# AutoSpielSimplified.net
KiCad netlist of a schematic drawn in EAGLE
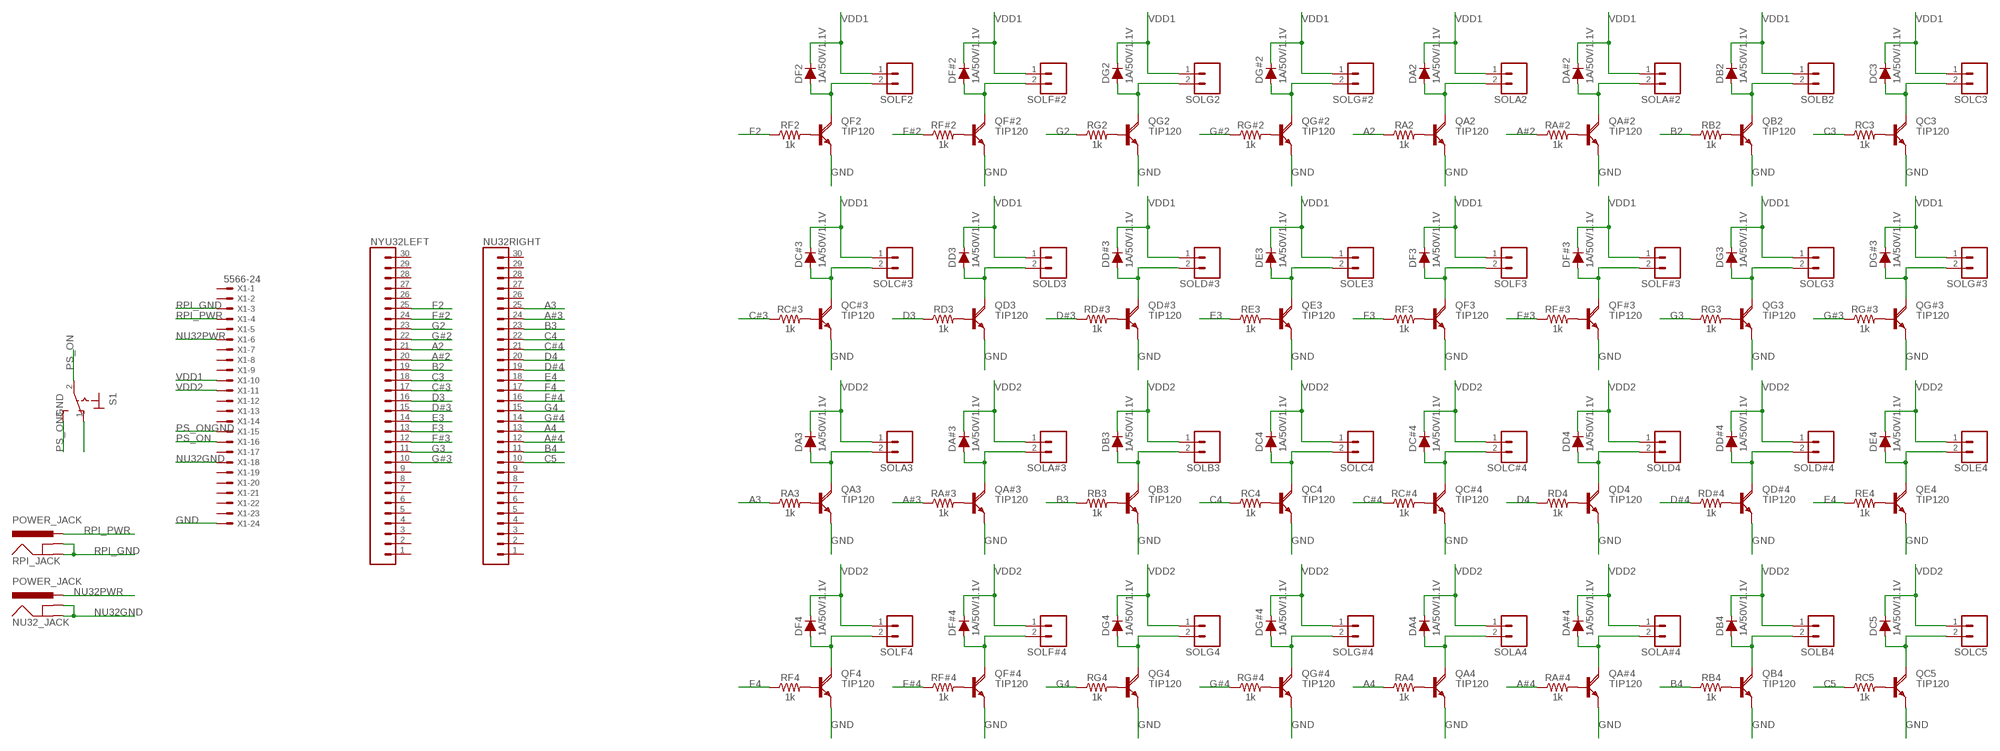
[diagram p0: schematic, sheet 1]

(export (version "E")
  (design (tool "Eeschema 10.0.6"))
  (components
    (comp (ref "DA#2")
      (value "1A/50V/1.1V")
      (footprint "eagle-import:DIODE-1N4001")
      (libsource (lib "eagle-import") (part "DIODE-PTH"))
    )
    (comp (ref "DA#3")
      (value "1A/50V/1.1V")
      (footprint "eagle-import:DIODE-1N4001")
      (libsource (lib "eagle-import") (part "DIODE-PTH"))
    )
    (comp (ref "DA#4")
      (value "1A/50V/1.1V")
      (footprint "eagle-import:DIODE-1N4001")
      (libsource (lib "eagle-import") (part "DIODE-PTH"))
    )
    (comp (ref "DA2")
      (value "1A/50V/1.1V")
      (footprint "eagle-import:DIODE-1N4001")
      (libsource (lib "eagle-import") (part "DIODE-PTH"))
    )
    (comp (ref "DA3")
      (value "1A/50V/1.1V")
      (footprint "eagle-import:DIODE-1N4001")
      (libsource (lib "eagle-import") (part "DIODE-PTH"))
    )
    (comp (ref "DA4")
      (value "1A/50V/1.1V")
      (footprint "eagle-import:DIODE-1N4001")
      (libsource (lib "eagle-import") (part "DIODE-PTH"))
    )
    (comp (ref "DB2")
      (value "1A/50V/1.1V")
      (footprint "eagle-import:DIODE-1N4001")
      (libsource (lib "eagle-import") (part "DIODE-PTH"))
    )
    (comp (ref "DB3")
      (value "1A/50V/1.1V")
      (footprint "eagle-import:DIODE-1N4001")
      (libsource (lib "eagle-import") (part "DIODE-PTH"))
    )
    (comp (ref "DB4")
      (value "1A/50V/1.1V")
      (footprint "eagle-import:DIODE-1N4001")
      (libsource (lib "eagle-import") (part "DIODE-PTH"))
    )
    (comp (ref "DC#3")
      (value "1A/50V/1.1V")
      (footprint "eagle-import:DIODE-1N4001")
      (libsource (lib "eagle-import") (part "DIODE-PTH"))
    )
    (comp (ref "DC#4")
      (value "1A/50V/1.1V")
      (footprint "eagle-import:DIODE-1N4001")
      (libsource (lib "eagle-import") (part "DIODE-PTH"))
    )
    (comp (ref "DC3")
      (value "1A/50V/1.1V")
      (footprint "eagle-import:DIODE-1N4001")
      (libsource (lib "eagle-import") (part "DIODE-PTH"))
    )
    (comp (ref "DC4")
      (value "1A/50V/1.1V")
      (footprint "eagle-import:DIODE-1N4001")
      (libsource (lib "eagle-import") (part "DIODE-PTH"))
    )
    (comp (ref "DC5")
      (value "1A/50V/1.1V")
      (footprint "eagle-import:DIODE-1N4001")
      (libsource (lib "eagle-import") (part "DIODE-PTH"))
    )
    (comp (ref "DD#3")
      (value "1A/50V/1.1V")
      (footprint "eagle-import:DIODE-1N4001")
      (libsource (lib "eagle-import") (part "DIODE-PTH"))
    )
    (comp (ref "DD#4")
      (value "1A/50V/1.1V")
      (footprint "eagle-import:DIODE-1N4001")
      (libsource (lib "eagle-import") (part "DIODE-PTH"))
    )
    (comp (ref "DD3")
      (value "1A/50V/1.1V")
      (footprint "eagle-import:DIODE-1N4001")
      (libsource (lib "eagle-import") (part "DIODE-PTH"))
    )
    (comp (ref "DD4")
      (value "1A/50V/1.1V")
      (footprint "eagle-import:DIODE-1N4001")
      (libsource (lib "eagle-import") (part "DIODE-PTH"))
    )
    (comp (ref "DE3")
      (value "1A/50V/1.1V")
      (footprint "eagle-import:DIODE-1N4001")
      (libsource (lib "eagle-import") (part "DIODE-PTH"))
    )
    (comp (ref "DE4")
      (value "1A/50V/1.1V")
      (footprint "eagle-import:DIODE-1N4001")
      (libsource (lib "eagle-import") (part "DIODE-PTH"))
    )
    (comp (ref "DF#2")
      (value "1A/50V/1.1V")
      (footprint "eagle-import:DIODE-1N4001")
      (libsource (lib "eagle-import") (part "DIODE-PTH"))
    )
    (comp (ref "DF#3")
      (value "1A/50V/1.1V")
      (footprint "eagle-import:DIODE-1N4001")
      (libsource (lib "eagle-import") (part "DIODE-PTH"))
    )
    (comp (ref "DF#4")
      (value "1A/50V/1.1V")
      (footprint "eagle-import:DIODE-1N4001")
      (libsource (lib "eagle-import") (part "DIODE-PTH"))
    )
    (comp (ref "DF2")
      (value "1A/50V/1.1V")
      (footprint "eagle-import:DIODE-1N4001")
      (libsource (lib "eagle-import") (part "DIODE-PTH"))
    )
    (comp (ref "DF3")
      (value "1A/50V/1.1V")
      (footprint "eagle-import:DIODE-1N4001")
      (libsource (lib "eagle-import") (part "DIODE-PTH"))
    )
    (comp (ref "DF4")
      (value "1A/50V/1.1V")
      (footprint "eagle-import:DIODE-1N4001")
      (libsource (lib "eagle-import") (part "DIODE-PTH"))
    )
    (comp (ref "DG#2")
      (value "1A/50V/1.1V")
      (footprint "eagle-import:DIODE-1N4001")
      (libsource (lib "eagle-import") (part "DIODE-PTH"))
    )
    (comp (ref "DG#3")
      (value "1A/50V/1.1V")
      (footprint "eagle-import:DIODE-1N4001")
      (libsource (lib "eagle-import") (part "DIODE-PTH"))
    )
    (comp (ref "DG#4")
      (value "1A/50V/1.1V")
      (footprint "eagle-import:DIODE-1N4001")
      (libsource (lib "eagle-import") (part "DIODE-PTH"))
    )
    (comp (ref "DG2")
      (value "1A/50V/1.1V")
      (footprint "eagle-import:DIODE-1N4001")
      (libsource (lib "eagle-import") (part "DIODE-PTH"))
    )
    (comp (ref "DG3")
      (value "1A/50V/1.1V")
      (footprint "eagle-import:DIODE-1N4001")
      (libsource (lib "eagle-import") (part "DIODE-PTH"))
    )
    (comp (ref "DG4")
      (value "1A/50V/1.1V")
      (footprint "eagle-import:DIODE-1N4001")
      (libsource (lib "eagle-import") (part "DIODE-PTH"))
    )
    (comp (ref "NU32RIGHT")
      (value "CONN_30")
      (footprint "eagle-import:1X30")
      (libsource (lib "eagle-import") (part "CONN_30"))
    )
    (comp (ref "NU32_JACK")
      (value "POWER_JACK")
      (footprint "eagle-import:POWER_JACK_PTH")
      (libsource (lib "eagle-import") (part "POWER_JACK"))
    )
    (comp (ref "NYU32LEFT")
      (value "CONN_30")
      (footprint "eagle-import:1X30")
      (libsource (lib "eagle-import") (part "CONN_30"))
    )
    (comp (ref "QA#2")
      (value "TIP120")
      (footprint "eagle-import:TO220AH")
      (libsource (lib "eagle-import") (part "TIP120"))
    )
    (comp (ref "QA#3")
      (value "TIP120")
      (footprint "eagle-import:TO220AH")
      (libsource (lib "eagle-import") (part "TIP120"))
    )
    (comp (ref "QA#4")
      (value "TIP120")
      (footprint "eagle-import:TO220AH")
      (libsource (lib "eagle-import") (part "TIP120"))
    )
    (comp (ref "QA2")
      (value "TIP120")
      (footprint "eagle-import:TO220AH")
      (libsource (lib "eagle-import") (part "TIP120"))
    )
    (comp (ref "QA3")
      (value "TIP120")
      (footprint "eagle-import:TO220AH")
      (libsource (lib "eagle-import") (part "TIP120"))
    )
    (comp (ref "QA4")
      (value "TIP120")
      (footprint "eagle-import:TO220AH")
      (libsource (lib "eagle-import") (part "TIP120"))
    )
    (comp (ref "QB2")
      (value "TIP120")
      (footprint "eagle-import:TO220AH")
      (libsource (lib "eagle-import") (part "TIP120"))
    )
    (comp (ref "QB3")
      (value "TIP120")
      (footprint "eagle-import:TO220AH")
      (libsource (lib "eagle-import") (part "TIP120"))
    )
    (comp (ref "QB4")
      (value "TIP120")
      (footprint "eagle-import:TO220AH")
      (libsource (lib "eagle-import") (part "TIP120"))
    )
    (comp (ref "QC#3")
      (value "TIP120")
      (footprint "eagle-import:TO220AH")
      (libsource (lib "eagle-import") (part "TIP120"))
    )
    (comp (ref "QC#4")
      (value "TIP120")
      (footprint "eagle-import:TO220AH")
      (libsource (lib "eagle-import") (part "TIP120"))
    )
    (comp (ref "QC3")
      (value "TIP120")
      (footprint "eagle-import:TO220AH")
      (libsource (lib "eagle-import") (part "TIP120"))
    )
    (comp (ref "QC4")
      (value "TIP120")
      (footprint "eagle-import:TO220AH")
      (libsource (lib "eagle-import") (part "TIP120"))
    )
    (comp (ref "QC5")
      (value "TIP120")
      (footprint "eagle-import:TO220AH")
      (libsource (lib "eagle-import") (part "TIP120"))
    )
    (comp (ref "QD#3")
      (value "TIP120")
      (footprint "eagle-import:TO220AH")
      (libsource (lib "eagle-import") (part "TIP120"))
    )
    (comp (ref "QD#4")
      (value "TIP120")
      (footprint "eagle-import:TO220AH")
      (libsource (lib "eagle-import") (part "TIP120"))
    )
    (comp (ref "QD3")
      (value "TIP120")
      (footprint "eagle-import:TO220AH")
      (libsource (lib "eagle-import") (part "TIP120"))
    )
    (comp (ref "QD4")
      (value "TIP120")
      (footprint "eagle-import:TO220AH")
      (libsource (lib "eagle-import") (part "TIP120"))
    )
    (comp (ref "QE3")
      (value "TIP120")
      (footprint "eagle-import:TO220AH")
      (libsource (lib "eagle-import") (part "TIP120"))
    )
    (comp (ref "QE4")
      (value "TIP120")
      (footprint "eagle-import:TO220AH")
      (libsource (lib "eagle-import") (part "TIP120"))
    )
    (comp (ref "QF#2")
      (value "TIP120")
      (footprint "eagle-import:TO220AH")
      (libsource (lib "eagle-import") (part "TIP120"))
    )
    (comp (ref "QF#3")
      (value "TIP120")
      (footprint "eagle-import:TO220AH")
      (libsource (lib "eagle-import") (part "TIP120"))
    )
    (comp (ref "QF#4")
      (value "TIP120")
      (footprint "eagle-import:TO220AH")
      (libsource (lib "eagle-import") (part "TIP120"))
    )
    (comp (ref "QF2")
      (value "TIP120")
      (footprint "eagle-import:TO220AH")
      (libsource (lib "eagle-import") (part "TIP120"))
    )
    (comp (ref "QF3")
      (value "TIP120")
      (footprint "eagle-import:TO220AH")
      (libsource (lib "eagle-import") (part "TIP120"))
    )
    (comp (ref "QF4")
      (value "TIP120")
      (footprint "eagle-import:TO220AH")
      (libsource (lib "eagle-import") (part "TIP120"))
    )
    (comp (ref "QG#2")
      (value "TIP120")
      (footprint "eagle-import:TO220AH")
      (libsource (lib "eagle-import") (part "TIP120"))
    )
    (comp (ref "QG#3")
      (value "TIP120")
      (footprint "eagle-import:TO220AH")
      (libsource (lib "eagle-import") (part "TIP120"))
    )
    (comp (ref "QG#4")
      (value "TIP120")
      (footprint "eagle-import:TO220AH")
      (libsource (lib "eagle-import") (part "TIP120"))
    )
    (comp (ref "QG2")
      (value "TIP120")
      (footprint "eagle-import:TO220AH")
      (libsource (lib "eagle-import") (part "TIP120"))
    )
    (comp (ref "QG3")
      (value "TIP120")
      (footprint "eagle-import:TO220AH")
      (libsource (lib "eagle-import") (part "TIP120"))
    )
    (comp (ref "QG4")
      (value "TIP120")
      (footprint "eagle-import:TO220AH")
      (libsource (lib "eagle-import") (part "TIP120"))
    )
    (comp (ref "RA#2")
      (value "1k")
      (footprint "eagle-import:AXIAL-0.3")
      (libsource (lib "eagle-import") (part "1KOHM-HORIZ-1/4W-5%"))
    )
    (comp (ref "RA#3")
      (value "1k")
      (footprint "eagle-import:AXIAL-0.3")
      (libsource (lib "eagle-import") (part "1KOHM-HORIZ-1/4W-5%"))
    )
    (comp (ref "RA#4")
      (value "1k")
      (footprint "eagle-import:AXIAL-0.3")
      (libsource (lib "eagle-import") (part "1KOHM-HORIZ-1/4W-5%"))
    )
    (comp (ref "RA2")
      (value "1k")
      (footprint "eagle-import:AXIAL-0.3")
      (libsource (lib "eagle-import") (part "1KOHM-HORIZ-1/4W-5%"))
    )
    (comp (ref "RA3")
      (value "1k")
      (footprint "eagle-import:AXIAL-0.3")
      (libsource (lib "eagle-import") (part "1KOHM-HORIZ-1/4W-5%"))
    )
    (comp (ref "RA4")
      (value "1k")
      (footprint "eagle-import:AXIAL-0.3")
      (libsource (lib "eagle-import") (part "1KOHM-HORIZ-1/4W-5%"))
    )
    (comp (ref "RB2")
      (value "1k")
      (footprint "eagle-import:AXIAL-0.3")
      (libsource (lib "eagle-import") (part "1KOHM-HORIZ-1/4W-5%"))
    )
    (comp (ref "RB3")
      (value "1k")
      (footprint "eagle-import:AXIAL-0.3")
      (libsource (lib "eagle-import") (part "1KOHM-HORIZ-1/4W-5%"))
    )
    (comp (ref "RB4")
      (value "1k")
      (footprint "eagle-import:AXIAL-0.3")
      (libsource (lib "eagle-import") (part "1KOHM-HORIZ-1/4W-5%"))
    )
    (comp (ref "RC#3")
      (value "1k")
      (footprint "eagle-import:AXIAL-0.3")
      (libsource (lib "eagle-import") (part "1KOHM-HORIZ-1/4W-5%"))
    )
    (comp (ref "RC#4")
      (value "1k")
      (footprint "eagle-import:AXIAL-0.3")
      (libsource (lib "eagle-import") (part "1KOHM-HORIZ-1/4W-5%"))
    )
    (comp (ref "RC3")
      (value "1k")
      (footprint "eagle-import:AXIAL-0.3")
      (libsource (lib "eagle-import") (part "1KOHM-HORIZ-1/4W-5%"))
    )
    (comp (ref "RC4")
      (value "1k")
      (footprint "eagle-import:AXIAL-0.3")
      (libsource (lib "eagle-import") (part "1KOHM-HORIZ-1/4W-5%"))
    )
    (comp (ref "RC5")
      (value "1k")
      (footprint "eagle-import:AXIAL-0.3")
      (libsource (lib "eagle-import") (part "1KOHM-HORIZ-1/4W-5%"))
    )
    (comp (ref "RD#3")
      (value "1k")
      (footprint "eagle-import:AXIAL-0.3")
      (libsource (lib "eagle-import") (part "1KOHM-HORIZ-1/4W-5%"))
    )
    (comp (ref "RD#4")
      (value "1k")
      (footprint "eagle-import:AXIAL-0.3")
      (libsource (lib "eagle-import") (part "1KOHM-HORIZ-1/4W-5%"))
    )
    (comp (ref "RD3")
      (value "1k")
      (footprint "eagle-import:AXIAL-0.3")
      (libsource (lib "eagle-import") (part "1KOHM-HORIZ-1/4W-5%"))
    )
    (comp (ref "RD4")
      (value "1k")
      (footprint "eagle-import:AXIAL-0.3")
      (libsource (lib "eagle-import") (part "1KOHM-HORIZ-1/4W-5%"))
    )
    (comp (ref "RE3")
      (value "1k")
      (footprint "eagle-import:AXIAL-0.3")
      (libsource (lib "eagle-import") (part "1KOHM-HORIZ-1/4W-5%"))
    )
    (comp (ref "RE4")
      (value "1k")
      (footprint "eagle-import:AXIAL-0.3")
      (libsource (lib "eagle-import") (part "1KOHM-HORIZ-1/4W-5%"))
    )
    (comp (ref "RF#2")
      (value "1k")
      (footprint "eagle-import:AXIAL-0.3")
      (libsource (lib "eagle-import") (part "1KOHM-HORIZ-1/4W-5%"))
    )
    (comp (ref "RF#3")
      (value "1k")
      (footprint "eagle-import:AXIAL-0.3")
      (libsource (lib "eagle-import") (part "1KOHM-HORIZ-1/4W-5%"))
    )
    (comp (ref "RF#4")
      (value "1k")
      (footprint "eagle-import:AXIAL-0.3")
      (libsource (lib "eagle-import") (part "1KOHM-HORIZ-1/4W-5%"))
    )
    (comp (ref "RF2")
      (value "1k")
      (footprint "eagle-import:AXIAL-0.3")
      (libsource (lib "eagle-import") (part "1KOHM-HORIZ-1/4W-5%"))
    )
    (comp (ref "RF3")
      (value "1k")
      (footprint "eagle-import:AXIAL-0.3")
      (libsource (lib "eagle-import") (part "1KOHM-HORIZ-1/4W-5%"))
    )
    (comp (ref "RF4")
      (value "1k")
      (footprint "eagle-import:AXIAL-0.3")
      (libsource (lib "eagle-import") (part "1KOHM-HORIZ-1/4W-5%"))
    )
    (comp (ref "RG#2")
      (value "1k")
      (footprint "eagle-import:AXIAL-0.3")
      (libsource (lib "eagle-import") (part "1KOHM-HORIZ-1/4W-5%"))
    )
    (comp (ref "RG#3")
      (value "1k")
      (footprint "eagle-import:AXIAL-0.3")
      (libsource (lib "eagle-import") (part "1KOHM-HORIZ-1/4W-5%"))
    )
    (comp (ref "RG#4")
      (value "1k")
      (footprint "eagle-import:AXIAL-0.3")
      (libsource (lib "eagle-import") (part "1KOHM-HORIZ-1/4W-5%"))
    )
    (comp (ref "RG2")
      (value "1k")
      (footprint "eagle-import:AXIAL-0.3")
      (libsource (lib "eagle-import") (part "1KOHM-HORIZ-1/4W-5%"))
    )
    (comp (ref "RG3")
      (value "1k")
      (footprint "eagle-import:AXIAL-0.3")
      (libsource (lib "eagle-import") (part "1KOHM-HORIZ-1/4W-5%"))
    )
    (comp (ref "RG4")
      (value "1k")
      (footprint "eagle-import:AXIAL-0.3")
      (libsource (lib "eagle-import") (part "1KOHM-HORIZ-1/4W-5%"))
    )
    (comp (ref "RPI_JACK")
      (value "POWER_JACK")
      (footprint "eagle-import:POWER_JACK_PTH")
      (libsource (lib "eagle-import") (part "POWER_JACK"))
    )
    (comp (ref "S1")
      (value "M9040P")
      (footprint "eagle-import:M9040P")
      (libsource (lib "eagle-import") (part "M9040P"))
    )
    (comp (ref "SOLA#2")
      (value "CONN_02PTH4")
      (footprint "eagle-import:1X02_XTRA_BIG")
      (libsource (lib "eagle-import") (part "CONN_02PTH4"))
    )
    (comp (ref "SOLA#3")
      (value "CONN_02PTH4")
      (footprint "eagle-import:1X02_XTRA_BIG")
      (libsource (lib "eagle-import") (part "CONN_02PTH4"))
    )
    (comp (ref "SOLA#4")
      (value "CONN_02PTH4")
      (footprint "eagle-import:1X02_XTRA_BIG")
      (libsource (lib "eagle-import") (part "CONN_02PTH4"))
    )
    (comp (ref "SOLA2")
      (value "CONN_02PTH4")
      (footprint "eagle-import:1X02_XTRA_BIG")
      (libsource (lib "eagle-import") (part "CONN_02PTH4"))
    )
    (comp (ref "SOLA3")
      (value "CONN_02PTH4")
      (footprint "eagle-import:1X02_XTRA_BIG")
      (libsource (lib "eagle-import") (part "CONN_02PTH4"))
    )
    (comp (ref "SOLA4")
      (value "CONN_02PTH4")
      (footprint "eagle-import:1X02_XTRA_BIG")
      (libsource (lib "eagle-import") (part "CONN_02PTH4"))
    )
    (comp (ref "SOLB2")
      (value "CONN_02PTH4")
      (footprint "eagle-import:1X02_XTRA_BIG")
      (libsource (lib "eagle-import") (part "CONN_02PTH4"))
    )
    (comp (ref "SOLB3")
      (value "CONN_02PTH4")
      (footprint "eagle-import:1X02_XTRA_BIG")
      (libsource (lib "eagle-import") (part "CONN_02PTH4"))
    )
    (comp (ref "SOLB4")
      (value "CONN_02PTH4")
      (footprint "eagle-import:1X02_XTRA_BIG")
      (libsource (lib "eagle-import") (part "CONN_02PTH4"))
    )
    (comp (ref "SOLC#3")
      (value "CONN_02PTH4")
      (footprint "eagle-import:1X02_XTRA_BIG")
      (libsource (lib "eagle-import") (part "CONN_02PTH4"))
    )
    (comp (ref "SOLC#4")
      (value "CONN_02PTH4")
      (footprint "eagle-import:1X02_XTRA_BIG")
      (libsource (lib "eagle-import") (part "CONN_02PTH4"))
    )
    (comp (ref "SOLC3")
      (value "CONN_02PTH4")
      (footprint "eagle-import:1X02_XTRA_BIG")
      (libsource (lib "eagle-import") (part "CONN_02PTH4"))
    )
    (comp (ref "SOLC4")
      (value "CONN_02PTH4")
      (footprint "eagle-import:1X02_XTRA_BIG")
      (libsource (lib "eagle-import") (part "CONN_02PTH4"))
    )
    (comp (ref "SOLC5")
      (value "CONN_02PTH4")
      (footprint "eagle-import:1X02_XTRA_BIG")
      (libsource (lib "eagle-import") (part "CONN_02PTH4"))
    )
    (comp (ref "SOLD#3")
      (value "CONN_02PTH4")
      (footprint "eagle-import:1X02_XTRA_BIG")
      (libsource (lib "eagle-import") (part "CONN_02PTH4"))
    )
    (comp (ref "SOLD#4")
      (value "CONN_02PTH4")
      (footprint "eagle-import:1X02_XTRA_BIG")
      (libsource (lib "eagle-import") (part "CONN_02PTH4"))
    )
    (comp (ref "SOLD3")
      (value "CONN_02PTH4")
      (footprint "eagle-import:1X02_XTRA_BIG")
      (libsource (lib "eagle-import") (part "CONN_02PTH4"))
    )
    (comp (ref "SOLD4")
      (value "CONN_02PTH4")
      (footprint "eagle-import:1X02_XTRA_BIG")
      (libsource (lib "eagle-import") (part "CONN_02PTH4"))
    )
    (comp (ref "SOLE3")
      (value "CONN_02PTH4")
      (footprint "eagle-import:1X02_XTRA_BIG")
      (libsource (lib "eagle-import") (part "CONN_02PTH4"))
    )
    (comp (ref "SOLE4")
      (value "CONN_02PTH4")
      (footprint "eagle-import:1X02_XTRA_BIG")
      (libsource (lib "eagle-import") (part "CONN_02PTH4"))
    )
    (comp (ref "SOLF#2")
      (value "CONN_02PTH4")
      (footprint "eagle-import:1X02_XTRA_BIG")
      (libsource (lib "eagle-import") (part "CONN_02PTH4"))
    )
    (comp (ref "SOLF#3")
      (value "CONN_02PTH4")
      (footprint "eagle-import:1X02_XTRA_BIG")
      (libsource (lib "eagle-import") (part "CONN_02PTH4"))
    )
    (comp (ref "SOLF#4")
      (value "CONN_02PTH4")
      (footprint "eagle-import:1X02_XTRA_BIG")
      (libsource (lib "eagle-import") (part "CONN_02PTH4"))
    )
    (comp (ref "SOLF2")
      (value "CONN_02PTH4")
      (footprint "eagle-import:1X02_XTRA_BIG")
      (libsource (lib "eagle-import") (part "CONN_02PTH4"))
    )
    (comp (ref "SOLF3")
      (value "CONN_02PTH4")
      (footprint "eagle-import:1X02_XTRA_BIG")
      (libsource (lib "eagle-import") (part "CONN_02PTH4"))
    )
    (comp (ref "SOLF4")
      (value "CONN_02PTH4")
      (footprint "eagle-import:1X02_XTRA_BIG")
      (libsource (lib "eagle-import") (part "CONN_02PTH4"))
    )
    (comp (ref "SOLG#2")
      (value "CONN_02PTH4")
      (footprint "eagle-import:1X02_XTRA_BIG")
      (libsource (lib "eagle-import") (part "CONN_02PTH4"))
    )
    (comp (ref "SOLG#3")
      (value "CONN_02PTH4")
      (footprint "eagle-import:1X02_XTRA_BIG")
      (libsource (lib "eagle-import") (part "CONN_02PTH4"))
    )
    (comp (ref "SOLG#4")
      (value "CONN_02PTH4")
      (footprint "eagle-import:1X02_XTRA_BIG")
      (libsource (lib "eagle-import") (part "CONN_02PTH4"))
    )
    (comp (ref "SOLG2")
      (value "CONN_02PTH4")
      (footprint "eagle-import:1X02_XTRA_BIG")
      (libsource (lib "eagle-import") (part "CONN_02PTH4"))
    )
    (comp (ref "SOLG3")
      (value "CONN_02PTH4")
      (footprint "eagle-import:1X02_XTRA_BIG")
      (libsource (lib "eagle-import") (part "CONN_02PTH4"))
    )
    (comp (ref "SOLG4")
      (value "CONN_02PTH4")
      (footprint "eagle-import:1X02_XTRA_BIG")
      (libsource (lib "eagle-import") (part "CONN_02PTH4"))
    )
    (comp (ref "X1")
      (value "5566-24")
      (footprint "eagle-import:5566-24")
      (fields (field (name "MF") "MOLEX"))
      (libsource (lib "eagle-import") (part "5566-24"))
    )
  )
  (nets
    (net (code "1") (name "/A#2") (class "Default")
      (node (ref "NYU32LEFT") (pin "20") (pinfunction "20_20") (pintype "passive"))
      (node (ref "RA#2") (pin "P$1") (pinfunction "1_P$1") (pintype "passive"))
    )
    (net (code "2") (name "/A#3") (class "Default")
      (node (ref "NU32RIGHT") (pin "24") (pinfunction "24_24") (pintype "passive"))
      (node (ref "RA#3") (pin "P$1") (pinfunction "1_P$1") (pintype "passive"))
    )
    (net (code "3") (name "/A#4") (class "Default")
      (node (ref "NU32RIGHT") (pin "12") (pinfunction "12_12") (pintype "passive"))
      (node (ref "RA#4") (pin "P$1") (pinfunction "1_P$1") (pintype "passive"))
    )
    (net (code "4") (name "/A2") (class "Default")
      (node (ref "NYU32LEFT") (pin "21") (pinfunction "21_21") (pintype "passive"))
      (node (ref "RA2") (pin "P$1") (pinfunction "1_P$1") (pintype "passive"))
    )
    (net (code "5") (name "/A3") (class "Default")
      (node (ref "NU32RIGHT") (pin "25") (pinfunction "25_25") (pintype "passive"))
      (node (ref "RA3") (pin "P$1") (pinfunction "1_P$1") (pintype "passive"))
    )
    (net (code "6") (name "/A4") (class "Default")
      (node (ref "NU32RIGHT") (pin "13") (pinfunction "13_13") (pintype "passive"))
      (node (ref "RA4") (pin "P$1") (pinfunction "1_P$1") (pintype "passive"))
    )
    (net (code "7") (name "/B2") (class "Default")
      (node (ref "NYU32LEFT") (pin "19") (pinfunction "19_19") (pintype "passive"))
      (node (ref "RB2") (pin "P$1") (pinfunction "1_P$1") (pintype "passive"))
    )
    (net (code "8") (name "/B3") (class "Default")
      (node (ref "NU32RIGHT") (pin "23") (pinfunction "23_23") (pintype "passive"))
      (node (ref "RB3") (pin "P$1") (pinfunction "1_P$1") (pintype "passive"))
    )
    (net (code "9") (name "/B4") (class "Default")
      (node (ref "NU32RIGHT") (pin "11") (pinfunction "11_11") (pintype "passive"))
      (node (ref "RB4") (pin "P$1") (pinfunction "1_P$1") (pintype "passive"))
    )
    (net (code "10") (name "/C#3") (class "Default")
      (node (ref "NYU32LEFT") (pin "17") (pinfunction "17_17") (pintype "passive"))
      (node (ref "RC#3") (pin "P$1") (pinfunction "1_P$1") (pintype "passive"))
    )
    (net (code "11") (name "/C#4") (class "Default")
      (node (ref "NU32RIGHT") (pin "21") (pinfunction "21_21") (pintype "passive"))
      (node (ref "RC#4") (pin "P$1") (pinfunction "1_P$1") (pintype "passive"))
    )
    (net (code "12") (name "/C3") (class "Default")
      (node (ref "NYU32LEFT") (pin "18") (pinfunction "18_18") (pintype "passive"))
      (node (ref "RC3") (pin "P$1") (pinfunction "1_P$1") (pintype "passive"))
    )
    (net (code "13") (name "/C4") (class "Default")
      (node (ref "NU32RIGHT") (pin "22") (pinfunction "22_22") (pintype "passive"))
      (node (ref "RC4") (pin "P$1") (pinfunction "1_P$1") (pintype "passive"))
    )
    (net (code "14") (name "/C5") (class "Default")
      (node (ref "NU32RIGHT") (pin "10") (pinfunction "10_10") (pintype "passive"))
      (node (ref "RC5") (pin "P$1") (pinfunction "1_P$1") (pintype "passive"))
    )
    (net (code "15") (name "/D#3") (class "Default")
      (node (ref "NYU32LEFT") (pin "15") (pinfunction "15_15") (pintype "passive"))
      (node (ref "RD#3") (pin "P$1") (pinfunction "1_P$1") (pintype "passive"))
    )
    (net (code "16") (name "/D#4") (class "Default")
      (node (ref "NU32RIGHT") (pin "19") (pinfunction "19_19") (pintype "passive"))
      (node (ref "RD#4") (pin "P$1") (pinfunction "1_P$1") (pintype "passive"))
    )
    (net (code "17") (name "/D3") (class "Default")
      (node (ref "NYU32LEFT") (pin "16") (pinfunction "16_16") (pintype "passive"))
      (node (ref "RD3") (pin "P$1") (pinfunction "1_P$1") (pintype "passive"))
    )
    (net (code "18") (name "/D4") (class "Default")
      (node (ref "NU32RIGHT") (pin "20") (pinfunction "20_20") (pintype "passive"))
      (node (ref "RD4") (pin "P$1") (pinfunction "1_P$1") (pintype "passive"))
    )
    (net (code "19") (name "/E3") (class "Default")
      (node (ref "NYU32LEFT") (pin "14") (pinfunction "14_14") (pintype "passive"))
      (node (ref "RE3") (pin "P$1") (pinfunction "1_P$1") (pintype "passive"))
    )
    (net (code "20") (name "/E4") (class "Default")
      (node (ref "NU32RIGHT") (pin "18") (pinfunction "18_18") (pintype "passive"))
      (node (ref "RE4") (pin "P$1") (pinfunction "1_P$1") (pintype "passive"))
    )
    (net (code "21") (name "/F#2") (class "Default")
      (node (ref "NYU32LEFT") (pin "24") (pinfunction "24_24") (pintype "passive"))
      (node (ref "RF#2") (pin "P$1") (pinfunction "1_P$1") (pintype "passive"))
    )
    (net (code "22") (name "/F#3") (class "Default")
      (node (ref "NYU32LEFT") (pin "12") (pinfunction "12_12") (pintype "passive"))
      (node (ref "RF#3") (pin "P$1") (pinfunction "1_P$1") (pintype "passive"))
    )
    (net (code "23") (name "/F#4") (class "Default")
      (node (ref "NU32RIGHT") (pin "16") (pinfunction "16_16") (pintype "passive"))
      (node (ref "RF#4") (pin "P$1") (pinfunction "1_P$1") (pintype "passive"))
    )
    (net (code "24") (name "/F2") (class "Default")
      (node (ref "NYU32LEFT") (pin "25") (pinfunction "25_25") (pintype "passive"))
      (node (ref "RF2") (pin "P$1") (pinfunction "1_P$1") (pintype "passive"))
    )
    (net (code "25") (name "/F3") (class "Default")
      (node (ref "NYU32LEFT") (pin "13") (pinfunction "13_13") (pintype "passive"))
      (node (ref "RF3") (pin "P$1") (pinfunction "1_P$1") (pintype "passive"))
    )
    (net (code "26") (name "/F4") (class "Default")
      (node (ref "NU32RIGHT") (pin "17") (pinfunction "17_17") (pintype "passive"))
      (node (ref "RF4") (pin "P$1") (pinfunction "1_P$1") (pintype "passive"))
    )
    (net (code "27") (name "/G#2") (class "Default")
      (node (ref "NYU32LEFT") (pin "22") (pinfunction "22_22") (pintype "passive"))
      (node (ref "RG#2") (pin "P$1") (pinfunction "1_P$1") (pintype "passive"))
    )
    (net (code "28") (name "/G#3") (class "Default")
      (node (ref "NYU32LEFT") (pin "10") (pinfunction "10_10") (pintype "passive"))
      (node (ref "RG#3") (pin "P$1") (pinfunction "1_P$1") (pintype "passive"))
    )
    (net (code "29") (name "/G#4") (class "Default")
      (node (ref "NU32RIGHT") (pin "14") (pinfunction "14_14") (pintype "passive"))
      (node (ref "RG#4") (pin "P$1") (pinfunction "1_P$1") (pintype "passive"))
    )
    (net (code "30") (name "/G2") (class "Default")
      (node (ref "NYU32LEFT") (pin "23") (pinfunction "23_23") (pintype "passive"))
      (node (ref "RG2") (pin "P$1") (pinfunction "1_P$1") (pintype "passive"))
    )
    (net (code "31") (name "/G3") (class "Default")
      (node (ref "NYU32LEFT") (pin "11") (pinfunction "11_11") (pintype "passive"))
      (node (ref "RG3") (pin "P$1") (pinfunction "1_P$1") (pintype "passive"))
    )
    (net (code "32") (name "/G4") (class "Default")
      (node (ref "NU32RIGHT") (pin "15") (pinfunction "15_15") (pintype "passive"))
      (node (ref "RG4") (pin "P$1") (pinfunction "1_P$1") (pintype "passive"))
    )
    (net (code "33") (name "/GND") (class "Default")
      (node (ref "QA#2") (pin "E") (pinfunction "E_E") (pintype "passive"))
      (node (ref "QA#3") (pin "E") (pinfunction "E_E") (pintype "passive"))
      (node (ref "QA#4") (pin "E") (pinfunction "E_E") (pintype "passive"))
      (node (ref "QA2") (pin "E") (pinfunction "E_E") (pintype "passive"))
      (node (ref "QA3") (pin "E") (pinfunction "E_E") (pintype "passive"))
      (node (ref "QA4") (pin "E") (pinfunction "E_E") (pintype "passive"))
      (node (ref "QB2") (pin "E") (pinfunction "E_E") (pintype "passive"))
      (node (ref "QB3") (pin "E") (pinfunction "E_E") (pintype "passive"))
      (node (ref "QB4") (pin "E") (pinfunction "E_E") (pintype "passive"))
      (node (ref "QC#3") (pin "E") (pinfunction "E_E") (pintype "passive"))
      (node (ref "QC#4") (pin "E") (pinfunction "E_E") (pintype "passive"))
      (node (ref "QC3") (pin "E") (pinfunction "E_E") (pintype "passive"))
      (node (ref "QC4") (pin "E") (pinfunction "E_E") (pintype "passive"))
      (node (ref "QC5") (pin "E") (pinfunction "E_E") (pintype "passive"))
      (node (ref "QD#3") (pin "E") (pinfunction "E_E") (pintype "passive"))
      (node (ref "QD#4") (pin "E") (pinfunction "E_E") (pintype "passive"))
      (node (ref "QD3") (pin "E") (pinfunction "E_E") (pintype "passive"))
      (node (ref "QD4") (pin "E") (pinfunction "E_E") (pintype "passive"))
      (node (ref "QE3") (pin "E") (pinfunction "E_E") (pintype "passive"))
      (node (ref "QE4") (pin "E") (pinfunction "E_E") (pintype "passive"))
      (node (ref "QF#2") (pin "E") (pinfunction "E_E") (pintype "passive"))
      (node (ref "QF#3") (pin "E") (pinfunction "E_E") (pintype "passive"))
      (node (ref "QF#4") (pin "E") (pinfunction "E_E") (pintype "passive"))
      (node (ref "QF2") (pin "E") (pinfunction "E_E") (pintype "passive"))
      (node (ref "QF3") (pin "E") (pinfunction "E_E") (pintype "passive"))
      (node (ref "QF4") (pin "E") (pinfunction "E_E") (pintype "passive"))
      (node (ref "QG#2") (pin "E") (pinfunction "E_E") (pintype "passive"))
      (node (ref "QG#3") (pin "E") (pinfunction "E_E") (pintype "passive"))
      (node (ref "QG#4") (pin "E") (pinfunction "E_E") (pintype "passive"))
      (node (ref "QG2") (pin "E") (pinfunction "E_E") (pintype "passive"))
      (node (ref "QG3") (pin "E") (pinfunction "E_E") (pintype "passive"))
      (node (ref "QG4") (pin "E") (pinfunction "E_E") (pintype "passive"))
      (node (ref "X1") (pin "24") (pinfunction "S_24") (pintype "passive"))
    )
    (net (code "34") (name "/NU32GND") (class "Default")
      (node (ref "NU32_JACK") (pin "GND") (pinfunction "GND_GND") (pintype "bidirectional"))
      (node (ref "NU32_JACK") (pin "GNDBREAK") (pinfunction "GNDBREAK_GNDBREAK") (pintype "bidirectional"))
      (node (ref "X1") (pin "18") (pinfunction "S_18") (pintype "passive"))
    )
    (net (code "35") (name "/NU32PWR") (class "Default")
      (node (ref "NU32_JACK") (pin "PWR") (pinfunction "PWR_PWR") (pintype "bidirectional"))
      (node (ref "X1") (pin "6") (pinfunction "S_6") (pintype "passive"))
    )
    (net (code "36") (name "/PS_ON") (class "Default")
      (node (ref "S1") (pin "2") (pinfunction "P_2") (pintype "passive"))
      (node (ref "X1") (pin "16") (pinfunction "S_16") (pintype "passive"))
    )
    (net (code "37") (name "/PS_ONGND") (class "Default")
      (node (ref "S1") (pin "3") (pinfunction "S_3") (pintype "passive"))
      (node (ref "X1") (pin "15") (pinfunction "S_15") (pintype "passive"))
    )
    (net (code "38") (name "/RPI_GND") (class "Default")
      (node (ref "RPI_JACK") (pin "GND") (pinfunction "GND_GND") (pintype "bidirectional"))
      (node (ref "RPI_JACK") (pin "GNDBREAK") (pinfunction "GNDBREAK_GNDBREAK") (pintype "bidirectional"))
      (node (ref "X1") (pin "3") (pinfunction "S_3") (pintype "passive"))
    )
    (net (code "39") (name "/RPI_PWR") (class "Default")
      (node (ref "RPI_JACK") (pin "PWR") (pinfunction "PWR_PWR") (pintype "bidirectional"))
      (node (ref "X1") (pin "4") (pinfunction "S_4") (pintype "passive"))
    )
    (net (code "40") (name "/VDD1") (class "Default")
      (node (ref "DA#2") (pin "C") (pinfunction "C_C") (pintype "passive"))
      (node (ref "DA2") (pin "C") (pinfunction "C_C") (pintype "passive"))
      (node (ref "DB2") (pin "C") (pinfunction "C_C") (pintype "passive"))
      (node (ref "DC#3") (pin "C") (pinfunction "C_C") (pintype "passive"))
      (node (ref "DC3") (pin "C") (pinfunction "C_C") (pintype "passive"))
      (node (ref "DD#3") (pin "C") (pinfunction "C_C") (pintype "passive"))
      (node (ref "DD3") (pin "C") (pinfunction "C_C") (pintype "passive"))
      (node (ref "DE3") (pin "C") (pinfunction "C_C") (pintype "passive"))
      (node (ref "DF#2") (pin "C") (pinfunction "C_C") (pintype "passive"))
      (node (ref "DF#3") (pin "C") (pinfunction "C_C") (pintype "passive"))
      (node (ref "DF2") (pin "C") (pinfunction "C_C") (pintype "passive"))
      (node (ref "DF3") (pin "C") (pinfunction "C_C") (pintype "passive"))
      (node (ref "DG#2") (pin "C") (pinfunction "C_C") (pintype "passive"))
      (node (ref "DG#3") (pin "C") (pinfunction "C_C") (pintype "passive"))
      (node (ref "DG2") (pin "C") (pinfunction "C_C") (pintype "passive"))
      (node (ref "DG3") (pin "C") (pinfunction "C_C") (pintype "passive"))
      (node (ref "SOLA#2") (pin "1") (pinfunction "1_1") (pintype "passive"))
      (node (ref "SOLA2") (pin "1") (pinfunction "1_1") (pintype "passive"))
      (node (ref "SOLB2") (pin "1") (pinfunction "1_1") (pintype "passive"))
      (node (ref "SOLC#3") (pin "1") (pinfunction "1_1") (pintype "passive"))
      (node (ref "SOLC3") (pin "1") (pinfunction "1_1") (pintype "passive"))
      (node (ref "SOLD#3") (pin "1") (pinfunction "1_1") (pintype "passive"))
      (node (ref "SOLD3") (pin "1") (pinfunction "1_1") (pintype "passive"))
      (node (ref "SOLE3") (pin "1") (pinfunction "1_1") (pintype "passive"))
      (node (ref "SOLF#2") (pin "1") (pinfunction "1_1") (pintype "passive"))
      (node (ref "SOLF#3") (pin "1") (pinfunction "1_1") (pintype "passive"))
      (node (ref "SOLF2") (pin "1") (pinfunction "1_1") (pintype "passive"))
      (node (ref "SOLF3") (pin "1") (pinfunction "1_1") (pintype "passive"))
      (node (ref "SOLG#2") (pin "1") (pinfunction "1_1") (pintype "passive"))
      (node (ref "SOLG#3") (pin "1") (pinfunction "1_1") (pintype "passive"))
      (node (ref "SOLG2") (pin "1") (pinfunction "1_1") (pintype "passive"))
      (node (ref "SOLG3") (pin "1") (pinfunction "1_1") (pintype "passive"))
      (node (ref "X1") (pin "10") (pinfunction "S_10") (pintype "passive"))
    )
    (net (code "41") (name "/VDD2") (class "Default")
      (node (ref "DA#3") (pin "C") (pinfunction "C_C") (pintype "passive"))
      (node (ref "DA#4") (pin "C") (pinfunction "C_C") (pintype "passive"))
      (node (ref "DA3") (pin "C") (pinfunction "C_C") (pintype "passive"))
      (node (ref "DA4") (pin "C") (pinfunction "C_C") (pintype "passive"))
      (node (ref "DB3") (pin "C") (pinfunction "C_C") (pintype "passive"))
      (node (ref "DB4") (pin "C") (pinfunction "C_C") (pintype "passive"))
      (node (ref "DC#4") (pin "C") (pinfunction "C_C") (pintype "passive"))
      (node (ref "DC4") (pin "C") (pinfunction "C_C") (pintype "passive"))
      (node (ref "DC5") (pin "C") (pinfunction "C_C") (pintype "passive"))
      (node (ref "DD#4") (pin "C") (pinfunction "C_C") (pintype "passive"))
      (node (ref "DD4") (pin "C") (pinfunction "C_C") (pintype "passive"))
      (node (ref "DE4") (pin "C") (pinfunction "C_C") (pintype "passive"))
      (node (ref "DF#4") (pin "C") (pinfunction "C_C") (pintype "passive"))
      (node (ref "DF4") (pin "C") (pinfunction "C_C") (pintype "passive"))
      (node (ref "DG#4") (pin "C") (pinfunction "C_C") (pintype "passive"))
      (node (ref "DG4") (pin "C") (pinfunction "C_C") (pintype "passive"))
      (node (ref "SOLA#3") (pin "1") (pinfunction "1_1") (pintype "passive"))
      (node (ref "SOLA#4") (pin "1") (pinfunction "1_1") (pintype "passive"))
      (node (ref "SOLA3") (pin "1") (pinfunction "1_1") (pintype "passive"))
      (node (ref "SOLA4") (pin "1") (pinfunction "1_1") (pintype "passive"))
      (node (ref "SOLB3") (pin "1") (pinfunction "1_1") (pintype "passive"))
      (node (ref "SOLB4") (pin "1") (pinfunction "1_1") (pintype "passive"))
      (node (ref "SOLC#4") (pin "1") (pinfunction "1_1") (pintype "passive"))
      (node (ref "SOLC4") (pin "1") (pinfunction "1_1") (pintype "passive"))
      (node (ref "SOLC5") (pin "1") (pinfunction "1_1") (pintype "passive"))
      (node (ref "SOLD#4") (pin "1") (pinfunction "1_1") (pintype "passive"))
      (node (ref "SOLD4") (pin "1") (pinfunction "1_1") (pintype "passive"))
      (node (ref "SOLE4") (pin "1") (pinfunction "1_1") (pintype "passive"))
      (node (ref "SOLF#4") (pin "1") (pinfunction "1_1") (pintype "passive"))
      (node (ref "SOLF4") (pin "1") (pinfunction "1_1") (pintype "passive"))
      (node (ref "SOLG#4") (pin "1") (pinfunction "1_1") (pintype "passive"))
      (node (ref "SOLG4") (pin "1") (pinfunction "1_1") (pintype "passive"))
      (node (ref "X1") (pin "11") (pinfunction "S_11") (pintype "passive"))
    )
    (net (code "42") (name "Net-(DA#2-PadA)") (class "Default")
      (node (ref "DA#2") (pin "A") (pinfunction "A_A") (pintype "passive"))
      (node (ref "QA#2") (pin "C") (pinfunction "C_C") (pintype "passive"))
      (node (ref "SOLA#2") (pin "2") (pinfunction "2_2") (pintype "passive"))
    )
    (net (code "43") (name "Net-(DA#3-PadA)") (class "Default")
      (node (ref "DA#3") (pin "A") (pinfunction "A_A") (pintype "passive"))
      (node (ref "QA#3") (pin "C") (pinfunction "C_C") (pintype "passive"))
      (node (ref "SOLA#3") (pin "2") (pinfunction "2_2") (pintype "passive"))
    )
    (net (code "44") (name "Net-(DA#4-PadA)") (class "Default")
      (node (ref "DA#4") (pin "A") (pinfunction "A_A") (pintype "passive"))
      (node (ref "QA#4") (pin "C") (pinfunction "C_C") (pintype "passive"))
      (node (ref "SOLA#4") (pin "2") (pinfunction "2_2") (pintype "passive"))
    )
    (net (code "45") (name "Net-(DA2-PadA)") (class "Default")
      (node (ref "DA2") (pin "A") (pinfunction "A_A") (pintype "passive"))
      (node (ref "QA2") (pin "C") (pinfunction "C_C") (pintype "passive"))
      (node (ref "SOLA2") (pin "2") (pinfunction "2_2") (pintype "passive"))
    )
    (net (code "46") (name "Net-(DA3-PadA)") (class "Default")
      (node (ref "DA3") (pin "A") (pinfunction "A_A") (pintype "passive"))
      (node (ref "QA3") (pin "C") (pinfunction "C_C") (pintype "passive"))
      (node (ref "SOLA3") (pin "2") (pinfunction "2_2") (pintype "passive"))
    )
    (net (code "47") (name "Net-(DA4-PadA)") (class "Default")
      (node (ref "DA4") (pin "A") (pinfunction "A_A") (pintype "passive"))
      (node (ref "QA4") (pin "C") (pinfunction "C_C") (pintype "passive"))
      (node (ref "SOLA4") (pin "2") (pinfunction "2_2") (pintype "passive"))
    )
    (net (code "48") (name "Net-(DB2-PadA)") (class "Default")
      (node (ref "DB2") (pin "A") (pinfunction "A_A") (pintype "passive"))
      (node (ref "QB2") (pin "C") (pinfunction "C_C") (pintype "passive"))
      (node (ref "SOLB2") (pin "2") (pinfunction "2_2") (pintype "passive"))
    )
    (net (code "49") (name "Net-(DB3-PadA)") (class "Default")
      (node (ref "DB3") (pin "A") (pinfunction "A_A") (pintype "passive"))
      (node (ref "QB3") (pin "C") (pinfunction "C_C") (pintype "passive"))
      (node (ref "SOLB3") (pin "2") (pinfunction "2_2") (pintype "passive"))
    )
    (net (code "50") (name "Net-(DB4-PadA)") (class "Default")
      (node (ref "DB4") (pin "A") (pinfunction "A_A") (pintype "passive"))
      (node (ref "QB4") (pin "C") (pinfunction "C_C") (pintype "passive"))
      (node (ref "SOLB4") (pin "2") (pinfunction "2_2") (pintype "passive"))
    )
    (net (code "51") (name "Net-(DC#3-PadA)") (class "Default")
      (node (ref "DC#3") (pin "A") (pinfunction "A_A") (pintype "passive"))
      (node (ref "QC#3") (pin "C") (pinfunction "C_C") (pintype "passive"))
      (node (ref "SOLC#3") (pin "2") (pinfunction "2_2") (pintype "passive"))
    )
    (net (code "52") (name "Net-(DC#4-PadA)") (class "Default")
      (node (ref "DC#4") (pin "A") (pinfunction "A_A") (pintype "passive"))
      (node (ref "QC#4") (pin "C") (pinfunction "C_C") (pintype "passive"))
      (node (ref "SOLC#4") (pin "2") (pinfunction "2_2") (pintype "passive"))
    )
    (net (code "53") (name "Net-(DC3-PadA)") (class "Default")
      (node (ref "DC3") (pin "A") (pinfunction "A_A") (pintype "passive"))
      (node (ref "QC3") (pin "C") (pinfunction "C_C") (pintype "passive"))
      (node (ref "SOLC3") (pin "2") (pinfunction "2_2") (pintype "passive"))
    )
    (net (code "54") (name "Net-(DC4-PadA)") (class "Default")
      (node (ref "DC4") (pin "A") (pinfunction "A_A") (pintype "passive"))
      (node (ref "QC4") (pin "C") (pinfunction "C_C") (pintype "passive"))
      (node (ref "SOLC4") (pin "2") (pinfunction "2_2") (pintype "passive"))
    )
    (net (code "55") (name "Net-(DC5-PadA)") (class "Default")
      (node (ref "DC5") (pin "A") (pinfunction "A_A") (pintype "passive"))
      (node (ref "QC5") (pin "C") (pinfunction "C_C") (pintype "passive"))
      (node (ref "SOLC5") (pin "2") (pinfunction "2_2") (pintype "passive"))
    )
    (net (code "56") (name "Net-(DD#3-PadA)") (class "Default")
      (node (ref "DD#3") (pin "A") (pinfunction "A_A") (pintype "passive"))
      (node (ref "QD#3") (pin "C") (pinfunction "C_C") (pintype "passive"))
      (node (ref "SOLD#3") (pin "2") (pinfunction "2_2") (pintype "passive"))
    )
    (net (code "57") (name "Net-(DD#4-PadA)") (class "Default")
      (node (ref "DD#4") (pin "A") (pinfunction "A_A") (pintype "passive"))
      (node (ref "QD#4") (pin "C") (pinfunction "C_C") (pintype "passive"))
      (node (ref "SOLD#4") (pin "2") (pinfunction "2_2") (pintype "passive"))
    )
    (net (code "58") (name "Net-(DD3-PadA)") (class "Default")
      (node (ref "DD3") (pin "A") (pinfunction "A_A") (pintype "passive"))
      (node (ref "QD3") (pin "C") (pinfunction "C_C") (pintype "passive"))
      (node (ref "SOLD3") (pin "2") (pinfunction "2_2") (pintype "passive"))
    )
    (net (code "59") (name "Net-(DD4-PadA)") (class "Default")
      (node (ref "DD4") (pin "A") (pinfunction "A_A") (pintype "passive"))
      (node (ref "QD4") (pin "C") (pinfunction "C_C") (pintype "passive"))
      (node (ref "SOLD4") (pin "2") (pinfunction "2_2") (pintype "passive"))
    )
    (net (code "60") (name "Net-(DE3-PadA)") (class "Default")
      (node (ref "DE3") (pin "A") (pinfunction "A_A") (pintype "passive"))
      (node (ref "QE3") (pin "C") (pinfunction "C_C") (pintype "passive"))
      (node (ref "SOLE3") (pin "2") (pinfunction "2_2") (pintype "passive"))
    )
    (net (code "61") (name "Net-(DE4-PadA)") (class "Default")
      (node (ref "DE4") (pin "A") (pinfunction "A_A") (pintype "passive"))
      (node (ref "QE4") (pin "C") (pinfunction "C_C") (pintype "passive"))
      (node (ref "SOLE4") (pin "2") (pinfunction "2_2") (pintype "passive"))
    )
    (net (code "62") (name "Net-(DF#2-PadA)") (class "Default")
      (node (ref "DF#2") (pin "A") (pinfunction "A_A") (pintype "passive"))
      (node (ref "QF#2") (pin "C") (pinfunction "C_C") (pintype "passive"))
      (node (ref "SOLF#2") (pin "2") (pinfunction "2_2") (pintype "passive"))
    )
    (net (code "63") (name "Net-(DF#3-PadA)") (class "Default")
      (node (ref "DF#3") (pin "A") (pinfunction "A_A") (pintype "passive"))
      (node (ref "QF#3") (pin "C") (pinfunction "C_C") (pintype "passive"))
      (node (ref "SOLF#3") (pin "2") (pinfunction "2_2") (pintype "passive"))
    )
    (net (code "64") (name "Net-(DF#4-PadA)") (class "Default")
      (node (ref "DF#4") (pin "A") (pinfunction "A_A") (pintype "passive"))
      (node (ref "QF#4") (pin "C") (pinfunction "C_C") (pintype "passive"))
      (node (ref "SOLF#4") (pin "2") (pinfunction "2_2") (pintype "passive"))
    )
    (net (code "65") (name "Net-(DF2-PadA)") (class "Default")
      (node (ref "DF2") (pin "A") (pinfunction "A_A") (pintype "passive"))
      (node (ref "QF2") (pin "C") (pinfunction "C_C") (pintype "passive"))
      (node (ref "SOLF2") (pin "2") (pinfunction "2_2") (pintype "passive"))
    )
    (net (code "66") (name "Net-(DF3-PadA)") (class "Default")
      (node (ref "DF3") (pin "A") (pinfunction "A_A") (pintype "passive"))
      (node (ref "QF3") (pin "C") (pinfunction "C_C") (pintype "passive"))
      (node (ref "SOLF3") (pin "2") (pinfunction "2_2") (pintype "passive"))
    )
    (net (code "67") (name "Net-(DF4-PadA)") (class "Default")
      (node (ref "DF4") (pin "A") (pinfunction "A_A") (pintype "passive"))
      (node (ref "QF4") (pin "C") (pinfunction "C_C") (pintype "passive"))
      (node (ref "SOLF4") (pin "2") (pinfunction "2_2") (pintype "passive"))
    )
    (net (code "68") (name "Net-(DG#2-PadA)") (class "Default")
      (node (ref "DG#2") (pin "A") (pinfunction "A_A") (pintype "passive"))
      (node (ref "QG#2") (pin "C") (pinfunction "C_C") (pintype "passive"))
      (node (ref "SOLG#2") (pin "2") (pinfunction "2_2") (pintype "passive"))
    )
    (net (code "69") (name "Net-(DG#3-PadA)") (class "Default")
      (node (ref "DG#3") (pin "A") (pinfunction "A_A") (pintype "passive"))
      (node (ref "QG#3") (pin "C") (pinfunction "C_C") (pintype "passive"))
      (node (ref "SOLG#3") (pin "2") (pinfunction "2_2") (pintype "passive"))
    )
    (net (code "70") (name "Net-(DG#4-PadA)") (class "Default")
      (node (ref "DG#4") (pin "A") (pinfunction "A_A") (pintype "passive"))
      (node (ref "QG#4") (pin "C") (pinfunction "C_C") (pintype "passive"))
      (node (ref "SOLG#4") (pin "2") (pinfunction "2_2") (pintype "passive"))
    )
    (net (code "71") (name "Net-(DG2-PadA)") (class "Default")
      (node (ref "DG2") (pin "A") (pinfunction "A_A") (pintype "passive"))
      (node (ref "QG2") (pin "C") (pinfunction "C_C") (pintype "passive"))
      (node (ref "SOLG2") (pin "2") (pinfunction "2_2") (pintype "passive"))
    )
    (net (code "72") (name "Net-(DG3-PadA)") (class "Default")
      (node (ref "DG3") (pin "A") (pinfunction "A_A") (pintype "passive"))
      (node (ref "QG3") (pin "C") (pinfunction "C_C") (pintype "passive"))
      (node (ref "SOLG3") (pin "2") (pinfunction "2_2") (pintype "passive"))
    )
    (net (code "73") (name "Net-(DG4-PadA)") (class "Default")
      (node (ref "DG4") (pin "A") (pinfunction "A_A") (pintype "passive"))
      (node (ref "QG4") (pin "C") (pinfunction "C_C") (pintype "passive"))
      (node (ref "SOLG4") (pin "2") (pinfunction "2_2") (pintype "passive"))
    )
    (net (code "74") (name "Net-(RA#2-2)") (class "Default")
      (node (ref "QA#2") (pin "B") (pinfunction "B_B") (pintype "passive"))
      (node (ref "RA#2") (pin "P$2") (pinfunction "2_P$2") (pintype "passive"))
    )
    (net (code "75") (name "Net-(RA#3-2)") (class "Default")
      (node (ref "QA#3") (pin "B") (pinfunction "B_B") (pintype "passive"))
      (node (ref "RA#3") (pin "P$2") (pinfunction "2_P$2") (pintype "passive"))
    )
    (net (code "76") (name "Net-(RA#4-2)") (class "Default")
      (node (ref "QA#4") (pin "B") (pinfunction "B_B") (pintype "passive"))
      (node (ref "RA#4") (pin "P$2") (pinfunction "2_P$2") (pintype "passive"))
    )
    (net (code "77") (name "Net-(RA2-2)") (class "Default")
      (node (ref "QA2") (pin "B") (pinfunction "B_B") (pintype "passive"))
      (node (ref "RA2") (pin "P$2") (pinfunction "2_P$2") (pintype "passive"))
    )
    (net (code "78") (name "Net-(RA3-2)") (class "Default")
      (node (ref "QA3") (pin "B") (pinfunction "B_B") (pintype "passive"))
      (node (ref "RA3") (pin "P$2") (pinfunction "2_P$2") (pintype "passive"))
    )
    (net (code "79") (name "Net-(RA4-2)") (class "Default")
      (node (ref "QA4") (pin "B") (pinfunction "B_B") (pintype "passive"))
      (node (ref "RA4") (pin "P$2") (pinfunction "2_P$2") (pintype "passive"))
    )
    (net (code "80") (name "Net-(RB2-2)") (class "Default")
      (node (ref "QB2") (pin "B") (pinfunction "B_B") (pintype "passive"))
      (node (ref "RB2") (pin "P$2") (pinfunction "2_P$2") (pintype "passive"))
    )
    (net (code "81") (name "Net-(RB3-2)") (class "Default")
      (node (ref "QB3") (pin "B") (pinfunction "B_B") (pintype "passive"))
      (node (ref "RB3") (pin "P$2") (pinfunction "2_P$2") (pintype "passive"))
    )
    (net (code "82") (name "Net-(RB4-2)") (class "Default")
      (node (ref "QB4") (pin "B") (pinfunction "B_B") (pintype "passive"))
      (node (ref "RB4") (pin "P$2") (pinfunction "2_P$2") (pintype "passive"))
    )
    (net (code "83") (name "Net-(RC#3-2)") (class "Default")
      (node (ref "QC#3") (pin "B") (pinfunction "B_B") (pintype "passive"))
      (node (ref "RC#3") (pin "P$2") (pinfunction "2_P$2") (pintype "passive"))
    )
    (net (code "84") (name "Net-(RC#4-2)") (class "Default")
      (node (ref "QC#4") (pin "B") (pinfunction "B_B") (pintype "passive"))
      (node (ref "RC#4") (pin "P$2") (pinfunction "2_P$2") (pintype "passive"))
    )
    (net (code "85") (name "Net-(RC3-2)") (class "Default")
      (node (ref "QC3") (pin "B") (pinfunction "B_B") (pintype "passive"))
      (node (ref "RC3") (pin "P$2") (pinfunction "2_P$2") (pintype "passive"))
    )
    (net (code "86") (name "Net-(RC4-2)") (class "Default")
      (node (ref "QC4") (pin "B") (pinfunction "B_B") (pintype "passive"))
      (node (ref "RC4") (pin "P$2") (pinfunction "2_P$2") (pintype "passive"))
    )
    (net (code "87") (name "Net-(RC5-2)") (class "Default")
      (node (ref "QC5") (pin "B") (pinfunction "B_B") (pintype "passive"))
      (node (ref "RC5") (pin "P$2") (pinfunction "2_P$2") (pintype "passive"))
    )
    (net (code "88") (name "Net-(RD#3-2)") (class "Default")
      (node (ref "QD#3") (pin "B") (pinfunction "B_B") (pintype "passive"))
      (node (ref "RD#3") (pin "P$2") (pinfunction "2_P$2") (pintype "passive"))
    )
    (net (code "89") (name "Net-(RD#4-2)") (class "Default")
      (node (ref "QD#4") (pin "B") (pinfunction "B_B") (pintype "passive"))
      (node (ref "RD#4") (pin "P$2") (pinfunction "2_P$2") (pintype "passive"))
    )
    (net (code "90") (name "Net-(RD3-2)") (class "Default")
      (node (ref "QD3") (pin "B") (pinfunction "B_B") (pintype "passive"))
      (node (ref "RD3") (pin "P$2") (pinfunction "2_P$2") (pintype "passive"))
    )
    (net (code "91") (name "Net-(RD4-2)") (class "Default")
      (node (ref "QD4") (pin "B") (pinfunction "B_B") (pintype "passive"))
      (node (ref "RD4") (pin "P$2") (pinfunction "2_P$2") (pintype "passive"))
    )
    (net (code "92") (name "Net-(RE3-2)") (class "Default")
      (node (ref "QE3") (pin "B") (pinfunction "B_B") (pintype "passive"))
      (node (ref "RE3") (pin "P$2") (pinfunction "2_P$2") (pintype "passive"))
    )
    (net (code "93") (name "Net-(RE4-2)") (class "Default")
      (node (ref "QE4") (pin "B") (pinfunction "B_B") (pintype "passive"))
      (node (ref "RE4") (pin "P$2") (pinfunction "2_P$2") (pintype "passive"))
    )
    (net (code "94") (name "Net-(RF#2-2)") (class "Default")
      (node (ref "QF#2") (pin "B") (pinfunction "B_B") (pintype "passive"))
      (node (ref "RF#2") (pin "P$2") (pinfunction "2_P$2") (pintype "passive"))
    )
    (net (code "95") (name "Net-(RF#3-2)") (class "Default")
      (node (ref "QF#3") (pin "B") (pinfunction "B_B") (pintype "passive"))
      (node (ref "RF#3") (pin "P$2") (pinfunction "2_P$2") (pintype "passive"))
    )
    (net (code "96") (name "Net-(RF#4-2)") (class "Default")
      (node (ref "QF#4") (pin "B") (pinfunction "B_B") (pintype "passive"))
      (node (ref "RF#4") (pin "P$2") (pinfunction "2_P$2") (pintype "passive"))
    )
    (net (code "97") (name "Net-(RF2-2)") (class "Default")
      (node (ref "QF2") (pin "B") (pinfunction "B_B") (pintype "passive"))
      (node (ref "RF2") (pin "P$2") (pinfunction "2_P$2") (pintype "passive"))
    )
    (net (code "98") (name "Net-(RF3-2)") (class "Default")
      (node (ref "QF3") (pin "B") (pinfunction "B_B") (pintype "passive"))
      (node (ref "RF3") (pin "P$2") (pinfunction "2_P$2") (pintype "passive"))
    )
    (net (code "99") (name "Net-(RF4-2)") (class "Default")
      (node (ref "QF4") (pin "B") (pinfunction "B_B") (pintype "passive"))
      (node (ref "RF4") (pin "P$2") (pinfunction "2_P$2") (pintype "passive"))
    )
    (net (code "100") (name "Net-(RG#2-2)") (class "Default")
      (node (ref "QG#2") (pin "B") (pinfunction "B_B") (pintype "passive"))
      (node (ref "RG#2") (pin "P$2") (pinfunction "2_P$2") (pintype "passive"))
    )
    (net (code "101") (name "Net-(RG#3-2)") (class "Default")
      (node (ref "QG#3") (pin "B") (pinfunction "B_B") (pintype "passive"))
      (node (ref "RG#3") (pin "P$2") (pinfunction "2_P$2") (pintype "passive"))
    )
    (net (code "102") (name "Net-(RG#4-2)") (class "Default")
      (node (ref "QG#4") (pin "B") (pinfunction "B_B") (pintype "passive"))
      (node (ref "RG#4") (pin "P$2") (pinfunction "2_P$2") (pintype "passive"))
    )
    (net (code "103") (name "Net-(RG2-2)") (class "Default")
      (node (ref "QG2") (pin "B") (pinfunction "B_B") (pintype "passive"))
      (node (ref "RG2") (pin "P$2") (pinfunction "2_P$2") (pintype "passive"))
    )
    (net (code "104") (name "Net-(RG3-2)") (class "Default")
      (node (ref "QG3") (pin "B") (pinfunction "B_B") (pintype "passive"))
      (node (ref "RG3") (pin "P$2") (pinfunction "2_P$2") (pintype "passive"))
    )
    (net (code "105") (name "Net-(RG4-2)") (class "Default")
      (node (ref "QG4") (pin "B") (pinfunction "B_B") (pintype "passive"))
      (node (ref "RG4") (pin "P$2") (pinfunction "2_P$2") (pintype "passive"))
    )
    (net (code "106") (name "unconnected-(NU32RIGHT-Pad1)") (class "Default")
      (node (ref "NU32RIGHT") (pin "1") (pinfunction "1_1") (pintype "passive"))
    )
    (net (code "107") (name "unconnected-(NU32RIGHT-Pad2)") (class "Default")
      (node (ref "NU32RIGHT") (pin "2") (pinfunction "2_2") (pintype "passive"))
    )
    (net (code "108") (name "unconnected-(NU32RIGHT-Pad3)") (class "Default")
      (node (ref "NU32RIGHT") (pin "3") (pinfunction "3_3") (pintype "passive"))
    )
    (net (code "109") (name "unconnected-(NU32RIGHT-Pad4)") (class "Default")
      (node (ref "NU32RIGHT") (pin "4") (pinfunction "4_4") (pintype "passive"))
    )
    (net (code "110") (name "unconnected-(NU32RIGHT-Pad5)") (class "Default")
      (node (ref "NU32RIGHT") (pin "5") (pinfunction "5_5") (pintype "passive"))
    )
    (net (code "111") (name "unconnected-(NU32RIGHT-Pad6)") (class "Default")
      (node (ref "NU32RIGHT") (pin "6") (pinfunction "6_6") (pintype "passive"))
    )
    (net (code "112") (name "unconnected-(NU32RIGHT-Pad7)") (class "Default")
      (node (ref "NU32RIGHT") (pin "7") (pinfunction "7_7") (pintype "passive"))
    )
    (net (code "113") (name "unconnected-(NU32RIGHT-Pad8)") (class "Default")
      (node (ref "NU32RIGHT") (pin "8") (pinfunction "8_8") (pintype "passive"))
    )
    (net (code "114") (name "unconnected-(NU32RIGHT-Pad9)") (class "Default")
      (node (ref "NU32RIGHT") (pin "9") (pinfunction "9_9") (pintype "passive"))
    )
    (net (code "115") (name "unconnected-(NU32RIGHT-Pad26)") (class "Default")
      (node (ref "NU32RIGHT") (pin "26") (pinfunction "26_26") (pintype "passive"))
    )
    (net (code "116") (name "unconnected-(NU32RIGHT-Pad27)") (class "Default")
      (node (ref "NU32RIGHT") (pin "27") (pinfunction "27_27") (pintype "passive"))
    )
    (net (code "117") (name "unconnected-(NU32RIGHT-Pad28)") (class "Default")
      (node (ref "NU32RIGHT") (pin "28") (pinfunction "28_28") (pintype "passive"))
    )
    (net (code "118") (name "unconnected-(NU32RIGHT-Pad29)") (class "Default")
      (node (ref "NU32RIGHT") (pin "29") (pinfunction "29_29") (pintype "passive"))
    )
    (net (code "119") (name "unconnected-(NU32RIGHT-Pad30)") (class "Default")
      (node (ref "NU32RIGHT") (pin "30") (pinfunction "30_30") (pintype "passive"))
    )
    (net (code "120") (name "unconnected-(NYU32LEFT-Pad1)") (class "Default")
      (node (ref "NYU32LEFT") (pin "1") (pinfunction "1_1") (pintype "passive"))
    )
    (net (code "121") (name "unconnected-(NYU32LEFT-Pad2)") (class "Default")
      (node (ref "NYU32LEFT") (pin "2") (pinfunction "2_2") (pintype "passive"))
    )
    (net (code "122") (name "unconnected-(NYU32LEFT-Pad3)") (class "Default")
      (node (ref "NYU32LEFT") (pin "3") (pinfunction "3_3") (pintype "passive"))
    )
    (net (code "123") (name "unconnected-(NYU32LEFT-Pad4)") (class "Default")
      (node (ref "NYU32LEFT") (pin "4") (pinfunction "4_4") (pintype "passive"))
    )
    (net (code "124") (name "unconnected-(NYU32LEFT-Pad5)") (class "Default")
      (node (ref "NYU32LEFT") (pin "5") (pinfunction "5_5") (pintype "passive"))
    )
    (net (code "125") (name "unconnected-(NYU32LEFT-Pad6)") (class "Default")
      (node (ref "NYU32LEFT") (pin "6") (pinfunction "6_6") (pintype "passive"))
    )
    (net (code "126") (name "unconnected-(NYU32LEFT-Pad7)") (class "Default")
      (node (ref "NYU32LEFT") (pin "7") (pinfunction "7_7") (pintype "passive"))
    )
    (net (code "127") (name "unconnected-(NYU32LEFT-Pad8)") (class "Default")
      (node (ref "NYU32LEFT") (pin "8") (pinfunction "8_8") (pintype "passive"))
    )
    (net (code "128") (name "unconnected-(NYU32LEFT-Pad9)") (class "Default")
      (node (ref "NYU32LEFT") (pin "9") (pinfunction "9_9") (pintype "passive"))
    )
    (net (code "129") (name "unconnected-(NYU32LEFT-Pad26)") (class "Default")
      (node (ref "NYU32LEFT") (pin "26") (pinfunction "26_26") (pintype "passive"))
    )
    (net (code "130") (name "unconnected-(NYU32LEFT-Pad27)") (class "Default")
      (node (ref "NYU32LEFT") (pin "27") (pinfunction "27_27") (pintype "passive"))
    )
    (net (code "131") (name "unconnected-(NYU32LEFT-Pad28)") (class "Default")
      (node (ref "NYU32LEFT") (pin "28") (pinfunction "28_28") (pintype "passive"))
    )
    (net (code "132") (name "unconnected-(NYU32LEFT-Pad29)") (class "Default")
      (node (ref "NYU32LEFT") (pin "29") (pinfunction "29_29") (pintype "passive"))
    )
    (net (code "133") (name "unconnected-(NYU32LEFT-Pad30)") (class "Default")
      (node (ref "NYU32LEFT") (pin "30") (pinfunction "30_30") (pintype "passive"))
    )
    (net (code "134") (name "unconnected-(S1-O-Pad1)") (class "Default")
      (node (ref "S1") (pin "1") (pinfunction "O_1") (pintype "passive"))
    )
    (net (code "135") (name "unconnected-(X1A-S-Pad1)") (class "Default")
      (node (ref "X1") (pin "1") (pinfunction "S_1") (pintype "passive"))
    )
    (net (code "136") (name "unconnected-(X1D-S-Pad12)") (class "Default")
      (node (ref "X1") (pin "12") (pinfunction "S_12") (pintype "passive"))
    )
    (net (code "137") (name "unconnected-(X1E-S-Pad13)") (class "Default")
      (node (ref "X1") (pin "13") (pinfunction "S_13") (pintype "passive"))
    )
    (net (code "138") (name "unconnected-(X1F-S-Pad14)") (class "Default")
      (node (ref "X1") (pin "14") (pinfunction "S_14") (pintype "passive"))
    )
    (net (code "139") (name "unconnected-(X1I-S-Pad17)") (class "Default")
      (node (ref "X1") (pin "17") (pinfunction "S_17") (pintype "passive"))
    )
    (net (code "140") (name "unconnected-(X1K-S-Pad19)") (class "Default")
      (node (ref "X1") (pin "19") (pinfunction "S_19") (pintype "passive"))
    )
    (net (code "141") (name "unconnected-(X1L-S-Pad2)") (class "Default")
      (node (ref "X1") (pin "2") (pinfunction "S_2") (pintype "passive"))
    )
    (net (code "142") (name "unconnected-(X1M-S-Pad20)") (class "Default")
      (node (ref "X1") (pin "20") (pinfunction "S_20") (pintype "passive"))
    )
    (net (code "143") (name "unconnected-(X1N-S-Pad21)") (class "Default")
      (node (ref "X1") (pin "21") (pinfunction "S_21") (pintype "passive"))
    )
    (net (code "144") (name "unconnected-(X1O-S-Pad22)") (class "Default")
      (node (ref "X1") (pin "22") (pinfunction "S_22") (pintype "passive"))
    )
    (net (code "145") (name "unconnected-(X1P-S-Pad23)") (class "Default")
      (node (ref "X1") (pin "23") (pinfunction "S_23") (pintype "passive"))
    )
    (net (code "146") (name "unconnected-(X1T-S-Pad5)") (class "Default")
      (node (ref "X1") (pin "5") (pinfunction "S_5") (pintype "passive"))
    )
    (net (code "147") (name "unconnected-(X1V-S-Pad7)") (class "Default")
      (node (ref "X1") (pin "7") (pinfunction "S_7") (pintype "passive"))
    )
    (net (code "148") (name "unconnected-(X1W-S-Pad8)") (class "Default")
      (node (ref "X1") (pin "8") (pinfunction "S_8") (pintype "passive"))
    )
    (net (code "149") (name "unconnected-(X1X-S-Pad9)") (class "Default")
      (node (ref "X1") (pin "9") (pinfunction "S_9") (pintype "passive"))
    )
  )
)
